# led.net
KiCad netlist of a schematic drawn in Altium Designer
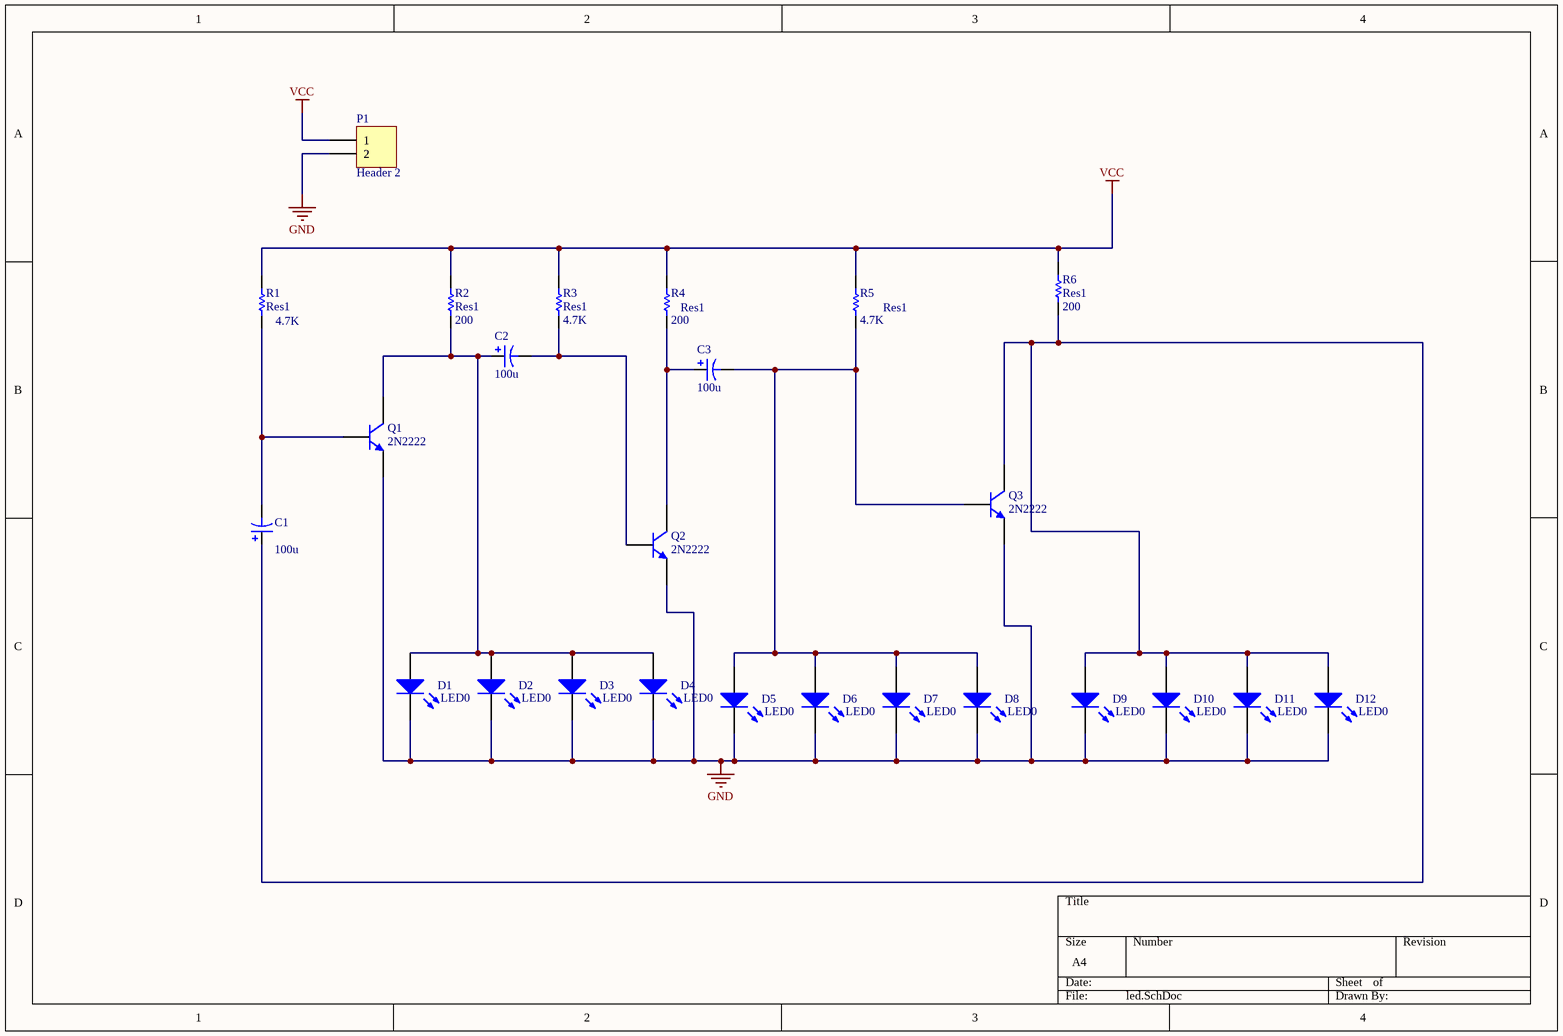
[diagram p0: led.SchDoc]

(export (version "E")
  (design (tool "Eeschema 10.0.6"))
  (components
    (comp (ref "C1")
      (value "100u")
      (footprint "RAD-0.1")
      (description "Polarized Capacitor (Radial)")
      (fields (field (name "Comment") "Cap Pol1") (field (name "PUBLISHER") "Altium Limited"))
      (libsource (lib "Miscellaneous Devices") (part "Cap Pol1"))
    )
    (comp (ref "C2")
      (value "100u")
      (footprint "RAD-0.1")
      (description "Polarized Capacitor (Radial)")
      (fields (field (name "Comment") "Cap Pol1") (field (name "PUBLISHER") "Altium Limited"))
      (libsource (lib "Miscellaneous Devices") (part "Cap Pol1"))
    )
    (comp (ref "C3")
      (value "100u")
      (footprint "RAD-0.1")
      (description "Polarized Capacitor (Radial)")
      (fields (field (name "Comment") "Cap Pol1") (field (name "PUBLISHER") "Altium Limited"))
      (libsource (lib "Miscellaneous Devices") (part "Cap Pol1"))
    )
    (comp (ref "D1")
      (value "LED0")
      (footprint "RAD-0.1")
      (description "Typical INFRARED GaAs LED")
      (fields (field (name "PUBLISHER") "Altium Limited"))
      (libsource (lib "Miscellaneous Devices") (part "LED0"))
    )
    (comp (ref "D2")
      (value "LED0")
      (footprint "RAD-0.1")
      (description "Typical INFRARED GaAs LED")
      (fields (field (name "PUBLISHER") "Altium Limited"))
      (libsource (lib "Miscellaneous Devices") (part "LED0"))
    )
    (comp (ref "D3")
      (value "LED0")
      (footprint "RAD-0.1")
      (description "Typical INFRARED GaAs LED")
      (fields (field (name "PUBLISHER") "Altium Limited"))
      (libsource (lib "Miscellaneous Devices") (part "LED0"))
    )
    (comp (ref "D4")
      (value "LED0")
      (footprint "RAD-0.1")
      (description "Typical INFRARED GaAs LED")
      (fields (field (name "PUBLISHER") "Altium Limited"))
      (libsource (lib "Miscellaneous Devices") (part "LED0"))
    )
    (comp (ref "D5")
      (value "LED0")
      (footprint "RAD-0.1")
      (description "Typical INFRARED GaAs LED")
      (fields (field (name "PUBLISHER") "Altium Limited"))
      (libsource (lib "Miscellaneous Devices") (part "LED0"))
    )
    (comp (ref "D6")
      (value "LED0")
      (footprint "RAD-0.1")
      (description "Typical INFRARED GaAs LED")
      (fields (field (name "PUBLISHER") "Altium Limited"))
      (libsource (lib "Miscellaneous Devices") (part "LED0"))
    )
    (comp (ref "D7")
      (value "LED0")
      (footprint "RAD-0.1")
      (description "Typical INFRARED GaAs LED")
      (fields (field (name "PUBLISHER") "Altium Limited"))
      (libsource (lib "Miscellaneous Devices") (part "LED0"))
    )
    (comp (ref "D8")
      (value "LED0")
      (footprint "RAD-0.1")
      (description "Typical INFRARED GaAs LED")
      (fields (field (name "PUBLISHER") "Altium Limited"))
      (libsource (lib "Miscellaneous Devices") (part "LED0"))
    )
    (comp (ref "D9")
      (value "LED0")
      (footprint "RAD-0.1")
      (description "Typical INFRARED GaAs LED")
      (fields (field (name "PUBLISHER") "Altium Limited"))
      (libsource (lib "Miscellaneous Devices") (part "LED0"))
    )
    (comp (ref "D10")
      (value "LED0")
      (footprint "RAD-0.1")
      (description "Typical INFRARED GaAs LED")
      (fields (field (name "PUBLISHER") "Altium Limited"))
      (libsource (lib "Miscellaneous Devices") (part "LED0"))
    )
    (comp (ref "D11")
      (value "LED0")
      (footprint "RAD-0.1")
      (description "Typical INFRARED GaAs LED")
      (fields (field (name "PUBLISHER") "Altium Limited"))
      (libsource (lib "Miscellaneous Devices") (part "LED0"))
    )
    (comp (ref "D12")
      (value "LED0")
      (footprint "RAD-0.1")
      (description "Typical INFRARED GaAs LED")
      (fields (field (name "PUBLISHER") "Altium Limited"))
      (libsource (lib "Miscellaneous Devices") (part "LED0"))
    )
    (comp (ref "P1")
      (value "Header 2")
      (footprint "HDR1X2")
      (description "Header, 2-Pin")
      (fields (field (name "PUBLISHER") "Altium Limited"))
      (libsource (lib "Miscellaneous Connectors") (part "Header 2"))
    )
    (comp (ref "Q1")
      (value "2N2222")
      (footprint "TO-39")
      (description "NPN General Purpose Amplifier")
      (fields (field (name "PUBLISHER") "Altium Limited"))
      (libsource (lib "Miscellaneous Devices") (part "2N3904"))
    )
    (comp (ref "Q2")
      (value "2N2222")
      (footprint "TO-39")
      (description "NPN General Purpose Amplifier")
      (fields (field (name "PUBLISHER") "Altium Limited"))
      (libsource (lib "Miscellaneous Devices") (part "2N3904"))
    )
    (comp (ref "Q3")
      (value "2N2222")
      (footprint "TO-39")
      (description "NPN General Purpose Amplifier")
      (fields (field (name "PUBLISHER") "Altium Limited"))
      (libsource (lib "Miscellaneous Devices") (part "2N3904"))
    )
    (comp (ref "R1")
      (value "Res1")
      (footprint "AXIAL-0.3")
      (description "Resistor")
      (fields (field (name "ALTIUM_VALUE") "4.7K") (field (name "PUBLISHER") "Altium Limited"))
      (libsource (lib "Miscellaneous Devices") (part "Res1"))
    )
    (comp (ref "R2")
      (value "Res1")
      (footprint "AXIAL-0.3")
      (description "Resistor")
      (fields (field (name "ALTIUM_VALUE") "200") (field (name "PUBLISHER") "Altium Limited"))
      (libsource (lib "Miscellaneous Devices") (part "Res1"))
    )
    (comp (ref "R3")
      (value "Res1")
      (footprint "AXIAL-0.3")
      (description "Resistor")
      (fields (field (name "ALTIUM_VALUE") "4.7K") (field (name "PUBLISHER") "Altium Limited"))
      (libsource (lib "Miscellaneous Devices") (part "Res1"))
    )
    (comp (ref "R4")
      (value "Res1")
      (footprint "AXIAL-0.3")
      (description "Resistor")
      (fields (field (name "ALTIUM_VALUE") "200") (field (name "PUBLISHER") "Altium Limited"))
      (libsource (lib "Miscellaneous Devices") (part "Res1"))
    )
    (comp (ref "R5")
      (value "Res1")
      (footprint "AXIAL-0.3")
      (description "Resistor")
      (fields (field (name "ALTIUM_VALUE") "4.7K") (field (name "PUBLISHER") "Altium Limited"))
      (libsource (lib "Miscellaneous Devices") (part "Res1"))
    )
    (comp (ref "R6")
      (value "Res1")
      (footprint "AXIAL-0.3")
      (description "Resistor")
      (fields (field (name "ALTIUM_VALUE") "200") (field (name "PUBLISHER") "Altium Limited"))
      (libsource (lib "Miscellaneous Devices") (part "Res1"))
    )
  )
  (nets
    (net (code "1") (name "GND") (class "Default")
      (node (ref "D1") (pin "2") (pinfunction "K_2") (pintype "passive"))
      (node (ref "D10") (pin "2") (pinfunction "K_2") (pintype "passive"))
      (node (ref "D11") (pin "2") (pinfunction "K_2") (pintype "passive"))
      (node (ref "D12") (pin "2") (pinfunction "K_2") (pintype "passive"))
      (node (ref "D2") (pin "2") (pinfunction "K_2") (pintype "passive"))
      (node (ref "D3") (pin "2") (pinfunction "K_2") (pintype "passive"))
      (node (ref "D4") (pin "2") (pinfunction "K_2") (pintype "passive"))
      (node (ref "D5") (pin "2") (pinfunction "K_2") (pintype "passive"))
      (node (ref "D6") (pin "2") (pinfunction "K_2") (pintype "passive"))
      (node (ref "D7") (pin "2") (pinfunction "K_2") (pintype "passive"))
      (node (ref "D8") (pin "2") (pinfunction "K_2") (pintype "passive"))
      (node (ref "D9") (pin "2") (pinfunction "K_2") (pintype "passive"))
      (node (ref "P1") (pin "2") (pinfunction "2_2") (pintype "passive"))
      (node (ref "Q1") (pin "1") (pinfunction "E_1") (pintype "passive"))
      (node (ref "Q2") (pin "1") (pinfunction "E_1") (pintype "passive"))
      (node (ref "Q3") (pin "1") (pinfunction "E_1") (pintype "passive"))
    )
    (net (code "2") (name "Net-(D1-A)") (class "Default")
      (node (ref "C2") (pin "1") (pinfunction "1_1") (pintype "passive"))
      (node (ref "D1") (pin "1") (pinfunction "A_1") (pintype "passive"))
      (node (ref "D2") (pin "1") (pinfunction "A_1") (pintype "passive"))
      (node (ref "D3") (pin "1") (pinfunction "A_1") (pintype "passive"))
      (node (ref "D4") (pin "1") (pinfunction "A_1") (pintype "passive"))
      (node (ref "Q1") (pin "3") (pinfunction "C_3") (pintype "passive"))
      (node (ref "R2") (pin "1") (pinfunction "1_1") (pintype "passive"))
    )
    (net (code "3") (name "Net-(D5-A)") (class "Default")
      (node (ref "C3") (pin "2") (pinfunction "2_2") (pintype "passive"))
      (node (ref "D5") (pin "1") (pinfunction "A_1") (pintype "passive"))
      (node (ref "D6") (pin "1") (pinfunction "A_1") (pintype "passive"))
      (node (ref "D7") (pin "1") (pinfunction "A_1") (pintype "passive"))
      (node (ref "D8") (pin "1") (pinfunction "A_1") (pintype "passive"))
      (node (ref "Q3") (pin "2") (pinfunction "B_2") (pintype "passive"))
      (node (ref "R5") (pin "1") (pinfunction "1_1") (pintype "passive"))
    )
    (net (code "4") (name "Net-(D10-A)") (class "Default")
      (node (ref "C1") (pin "1") (pinfunction "1_1") (pintype "passive"))
      (node (ref "D10") (pin "1") (pinfunction "A_1") (pintype "passive"))
      (node (ref "D11") (pin "1") (pinfunction "A_1") (pintype "passive"))
      (node (ref "D12") (pin "1") (pinfunction "A_1") (pintype "passive"))
      (node (ref "D9") (pin "1") (pinfunction "A_1") (pintype "passive"))
      (node (ref "Q3") (pin "3") (pinfunction "C_3") (pintype "passive"))
      (node (ref "R6") (pin "1") (pinfunction "1_1") (pintype "passive"))
    )
    (net (code "5") (name "Net-(Q1-B)") (class "Default")
      (node (ref "C1") (pin "2") (pinfunction "2_2") (pintype "passive"))
      (node (ref "Q1") (pin "2") (pinfunction "B_2") (pintype "passive"))
      (node (ref "R1") (pin "1") (pinfunction "1_1") (pintype "passive"))
    )
    (net (code "6") (name "Net-(Q2-B)") (class "Default")
      (node (ref "C2") (pin "2") (pinfunction "2_2") (pintype "passive"))
      (node (ref "Q2") (pin "2") (pinfunction "B_2") (pintype "passive"))
      (node (ref "R3") (pin "1") (pinfunction "1_1") (pintype "passive"))
    )
    (net (code "7") (name "Net-(Q2-C)") (class "Default")
      (node (ref "C3") (pin "1") (pinfunction "1_1") (pintype "passive"))
      (node (ref "Q2") (pin "3") (pinfunction "C_3") (pintype "passive"))
      (node (ref "R4") (pin "1") (pinfunction "1_1") (pintype "passive"))
    )
    (net (code "8") (name "VCC") (class "Default")
      (node (ref "P1") (pin "1") (pinfunction "1_1") (pintype "passive"))
      (node (ref "R1") (pin "2") (pinfunction "2_2") (pintype "passive"))
      (node (ref "R2") (pin "2") (pinfunction "2_2") (pintype "passive"))
      (node (ref "R3") (pin "2") (pinfunction "2_2") (pintype "passive"))
      (node (ref "R4") (pin "2") (pinfunction "2_2") (pintype "passive"))
      (node (ref "R5") (pin "2") (pinfunction "2_2") (pintype "passive"))
      (node (ref "R6") (pin "2") (pinfunction "2_2") (pintype "passive"))
    )
  )
)
